# Regulator.net
KiCad netlist of a schematic drawn in Altium Designer
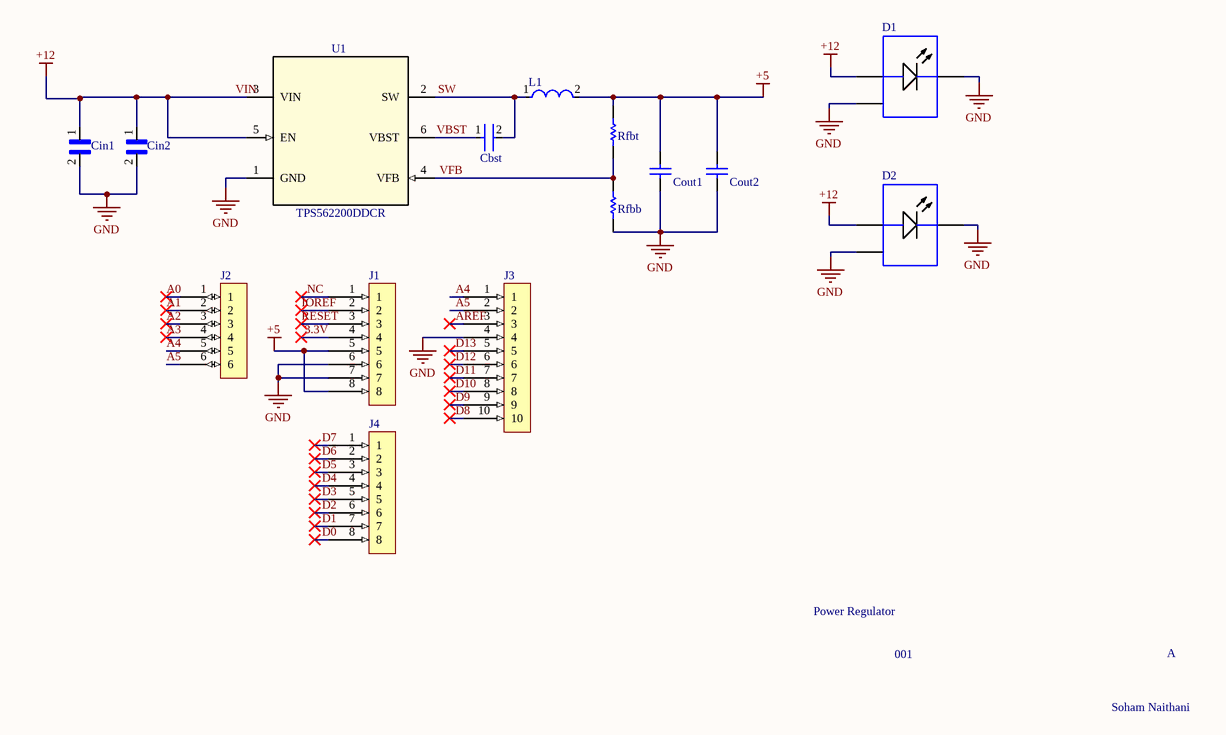
[diagram p0: Regulator.SchDoc]

(export (version "E")
  (design (tool "Eeschema 10.0.6"))
  (components
    (comp (ref "Cbst")
      (value "CC0805KRX7R8BB104")
      (footprint "FP-CC0805-0_85-MFG")
      (description "CAP CER 0.1UF 25V X7R 0805")
      (fields (field (name "TOLERANCE") "0.1") (field (name "MANUFACTURER") "Yageo"))
      (libsource (lib "Altium Content Vault") (part "11868f565c42a9108669ba33697ecf6"))
    )
    (comp (ref "Cin1")
      (value "C2012X5R1V106K085AC")
      (footprint "CAPC2012X100N")
      (description "10ÂµF Â±10% 35V Ceramic Capacitor X5R 0805 (2012 Metric)")
      (fields (field (name "MF") "TDK"))
      (libsource (lib "C2012X5R1V106K085AC") (part "C2012X5R1V106K085AC"))
    )
    (comp (ref "Cin2")
      (value "C2012X5R1V106K085AC")
      (footprint "CAPC2012X100N")
      (description "10ÂµF Â±10% 35V Ceramic Capacitor X5R 0805 (2012 Metric)")
      (fields (field (name "MF") "TDK"))
      (libsource (lib "C2012X5R1V106K085AC") (part "C2012X5R1V106K085AC"))
    )
    (comp (ref "Cout1")
      (value "C1608X5R1A226M080AC")
      (footprint "CAPC1608X100X20ML10")
      (description "Chip Capacitor, 22 uF, +/- 20%, 10 V, -55 to 85 degC, 0603 (1608 Metric), RoHS, Tape and Reel")
      (fields (field (name "MANUFACTURER") "TDK") (field (name "TOLERANCE") "±20%"))
      (libsource (lib "Altium Content Vault") (part "CAP-NP-2"))
    )
    (comp (ref "Cout2")
      (value "C1608X5R1A226M080AC")
      (footprint "CAPC1608X100X20ML10")
      (description "Chip Capacitor, 22 uF, +/- 20%, 10 V, -55 to 85 degC, 0603 (1608 Metric), RoHS, Tape and Reel")
      (fields (field (name "MANUFACTURER") "TDK") (field (name "TOLERANCE") "±20%"))
      (libsource (lib "Altium Content Vault") (part "CAP-NP-2"))
    )
    (comp (ref "D1")
      (value "MKRAWT-00-0000-0D0HG235H")
      (footprint "CREE-MK-R-2_V")
      (description "LED, White, 12 V, 2-Pin SMD, RoHS, Tape and Reel")
      (libsource (lib "Altium Content Vault") (part "LED_WHITE-3"))
    )
    (comp (ref "D2")
      (value "MKRAWT-00-0000-0D0HG235H")
      (footprint "CREE-MK-R-2_V")
      (description "LED, White, 12 V, 2-Pin SMD, RoHS, Tape and Reel")
      (libsource (lib "Altium Content Vault") (part "LED_WHITE-3"))
    )
    (comp (ref "J1")
      (value "8-Pin-Header")
      (footprint "8-Pin-Header-Footprint-1")
      (description "simple 8 pin header")
      (libsource (lib "Soham Naithani") (part "8-Pin-Header-Symbol-1"))
    )
    (comp (ref "J2")
      (value "6-Pin-Header")
      (footprint "6-PINHEADER-Footprint-1")
      (description "Simple 6 pin header")
      (libsource (lib "Soham Naithani") (part "6-PINHEADER-Symbol-1"))
    )
    (comp (ref "J3")
      (value "10-Pin-Header")
      (footprint "10-Pin-Header-Footprint-1")
      (description "Simple 10 pin header")
      (libsource (lib "Soham Naithani") (part "10-Pin-Header-Symbol-1"))
    )
    (comp (ref "J4")
      (value "8-Pin-Header")
      (footprint "8-Pin-Header-Footprint-1")
      (description "simple 8 pin header")
      (libsource (lib "Soham Naithani") (part "8-Pin-Header-Symbol-1"))
    )
    (comp (ref "L1")
      (value "NRS8030T3R3MJGJ")
      (footprint "FP-NRS8030-MFG")
      (description "Inductor Power Shielded Wirewound 3.3uH 20% 100KHz Ferrite 4.2A 24.7mΩ DCR T/R")
      (fields (field (name "TOLERANCE") "20%"))
      (libsource (lib "Altium Content Vault") (part "725321dda6339637d4d059423bc1c3c"))
    )
    (comp (ref "Rfbb")
      (value "ERJ2RKF1002X")
      (footprint "RESC1005X40X25LL05T05")
      (description "Chip Resistor, 10 KOhm, +/- 1%, 0.1 W, -55 to 155 degC, 0402 (1005 Metric), RoHS, Tape and Reel")
      (fields (field (name "TOLERANCE") "1%") (field (name "MANUFACTURER") "Panasonic"))
      (libsource (lib "Altium Content Vault") (part "RES-2"))
    )
    (comp (ref "Rfbt")
      (value "CRCW020156K2FNED")
      (footprint "RESC0603X28X15NL05T05")
      (fields (field (name "MANUFACTURER") "Vishay Dale"))
      (libsource (lib "Altium Content Vault") (part "RES"))
    )
    (comp (ref "U1")
      (value "TPS562200DDCR")
      (footprint "DDC0006A")
      (description "No Description Available")
      (fields
        (field (name "PARTNUMBER") "TPS562200DDC")
        (field (name "MANUFACTURER") "Texas Instruments")
        (field (name "COPYRIGHT") "Copyright (C) 2023 Ultra Librarian. All rights reserved.")
        (field (name "MODIFIEDDATE") "Not shown in title block")
        (field (name "APPROVEDBY") "Not shown in title block")
        (field (name "CHECKEDBY") "Not shown in title block")
        (field (name "AUTHOR") "Not shown in title block")
        (field (name "ENGINEER") "Not shown in title block")
        (field (name "SYMBOLCREATOR") "a0411947")
        (field (name "PUBLISHER") "Texas Instruments")
      )
      (libsource (lib "TPS562200DDCR") (part "TPS562200DDCR"))
    )
  )
  (nets
    (net (code "1") (name "+5") (class "Default")
      (node (ref "Cout1") (pin "2") (pinfunction "2_2") (pintype "passive"))
      (node (ref "Cout2") (pin "2") (pinfunction "2_2") (pintype "passive"))
      (node (ref "J1") (pin "5") (pinfunction "5_5") (pintype "input"))
      (node (ref "J1") (pin "8") (pinfunction "8_8") (pintype "input"))
      (node (ref "L1") (pin "2") (pinfunction "2_2") (pintype "passive"))
      (node (ref "Rfbt") (pin "2") (pinfunction "2_2") (pintype "passive"))
    )
    (net (code "2") (name "+12") (class "Default")
      (node (ref "Cin1") (pin "1") (pinfunction "1_1") (pintype "passive"))
      (node (ref "Cin2") (pin "1") (pinfunction "1_1") (pintype "passive"))
      (node (ref "D1") (pin "1") (pinfunction "A_1") (pintype "passive"))
      (node (ref "D2") (pin "1") (pinfunction "A_1") (pintype "passive"))
      (node (ref "U1") (pin "3") (pinfunction "VIN_3") (pintype "power_in"))
      (node (ref "U1") (pin "5") (pinfunction "EN_5") (pintype "input"))
    )
    (net (code "3") (name "/3.3V") (class "Default")
      (node (ref "J1") (pin "4") (pinfunction "4_4") (pintype "input+no_connect"))
    )
    (net (code "4") (name "/A0") (class "Default")
      (node (ref "J2") (pin "1") (pinfunction "1_1") (pintype "bidirectional+no_connect"))
    )
    (net (code "5") (name "/A1") (class "Default")
      (node (ref "J2") (pin "2") (pinfunction "2_2") (pintype "bidirectional+no_connect"))
    )
    (net (code "6") (name "/A2") (class "Default")
      (node (ref "J2") (pin "3") (pinfunction "3_3") (pintype "bidirectional+no_connect"))
    )
    (net (code "7") (name "/A3") (class "Default")
      (node (ref "J2") (pin "4") (pinfunction "4_4") (pintype "bidirectional+no_connect"))
    )
    (net (code "8") (name "/A4") (class "Default")
      (node (ref "J2") (pin "5") (pinfunction "5_5") (pintype "bidirectional"))
      (node (ref "J3") (pin "1") (pinfunction "1_1") (pintype "input"))
    )
    (net (code "9") (name "/A5") (class "Default")
      (node (ref "J2") (pin "6") (pinfunction "6_6") (pintype "bidirectional"))
      (node (ref "J3") (pin "2") (pinfunction "2_2") (pintype "input"))
    )
    (net (code "10") (name "/AREF") (class "Default")
      (node (ref "J3") (pin "3") (pinfunction "3_3") (pintype "input+no_connect"))
    )
    (net (code "11") (name "/D0") (class "Default")
      (node (ref "J4") (pin "8") (pinfunction "8_8") (pintype "input+no_connect"))
    )
    (net (code "12") (name "/D1") (class "Default")
      (node (ref "J4") (pin "7") (pinfunction "7_7") (pintype "input+no_connect"))
    )
    (net (code "13") (name "/D2") (class "Default")
      (node (ref "J4") (pin "6") (pinfunction "6_6") (pintype "input+no_connect"))
    )
    (net (code "14") (name "/D3") (class "Default")
      (node (ref "J4") (pin "5") (pinfunction "5_5") (pintype "input+no_connect"))
    )
    (net (code "15") (name "/D4") (class "Default")
      (node (ref "J4") (pin "4") (pinfunction "4_4") (pintype "input+no_connect"))
    )
    (net (code "16") (name "/D5") (class "Default")
      (node (ref "J4") (pin "3") (pinfunction "3_3") (pintype "input+no_connect"))
    )
    (net (code "17") (name "/D6") (class "Default")
      (node (ref "J4") (pin "2") (pinfunction "2_2") (pintype "input+no_connect"))
    )
    (net (code "18") (name "/D7") (class "Default")
      (node (ref "J4") (pin "1") (pinfunction "1_1") (pintype "input+no_connect"))
    )
    (net (code "19") (name "/D8") (class "Default")
      (node (ref "J3") (pin "10") (pinfunction "10_10") (pintype "input+no_connect"))
    )
    (net (code "20") (name "/D9") (class "Default")
      (node (ref "J3") (pin "9") (pinfunction "9_9") (pintype "input+no_connect"))
    )
    (net (code "21") (name "/D10") (class "Default")
      (node (ref "J3") (pin "8") (pinfunction "8_8") (pintype "input+no_connect"))
    )
    (net (code "22") (name "/D11") (class "Default")
      (node (ref "J3") (pin "7") (pinfunction "7_7") (pintype "input+no_connect"))
    )
    (net (code "23") (name "/D12") (class "Default")
      (node (ref "J3") (pin "6") (pinfunction "6_6") (pintype "input+no_connect"))
    )
    (net (code "24") (name "/D13") (class "Default")
      (node (ref "J3") (pin "5") (pinfunction "5_5") (pintype "input+no_connect"))
    )
    (net (code "25") (name "/IOREF") (class "Default")
      (node (ref "J1") (pin "2") (pinfunction "2_2") (pintype "input+no_connect"))
    )
    (net (code "26") (name "/NC") (class "Default")
      (node (ref "J1") (pin "1") (pinfunction "1_1") (pintype "input+no_connect"))
    )
    (net (code "27") (name "/RESET") (class "Default")
      (node (ref "J1") (pin "3") (pinfunction "3_3") (pintype "input+no_connect"))
    )
    (net (code "28") (name "/SW") (class "Default")
      (node (ref "Cbst") (pin "2") (pinfunction "2_2") (pintype "passive"))
      (node (ref "L1") (pin "1") (pinfunction "1_1") (pintype "passive"))
      (node (ref "U1") (pin "2") (pinfunction "SW_2") (pintype "power_in"))
    )
    (net (code "29") (name "/VBST") (class "Default")
      (node (ref "Cbst") (pin "1") (pinfunction "1_1") (pintype "passive"))
      (node (ref "U1") (pin "6") (pinfunction "VBST_6") (pintype "power_in"))
    )
    (net (code "30") (name "/VFB") (class "Default")
      (node (ref "Rfbb") (pin "2") (pinfunction "2_2") (pintype "passive"))
      (node (ref "Rfbt") (pin "1") (pinfunction "1_1") (pintype "passive"))
      (node (ref "U1") (pin "4") (pinfunction "VFB_4") (pintype "input"))
    )
    (net (code "31") (name "GND") (class "Default")
      (node (ref "Cin1") (pin "2") (pinfunction "2_2") (pintype "passive"))
      (node (ref "Cin2") (pin "2") (pinfunction "2_2") (pintype "passive"))
      (node (ref "Cout1") (pin "1") (pinfunction "1_1") (pintype "passive"))
      (node (ref "Cout2") (pin "1") (pinfunction "1_1") (pintype "passive"))
      (node (ref "D1") (pin "2") (pinfunction "K_2") (pintype "passive"))
      (node (ref "D1") (pin "3") (pinfunction "EP_3") (pintype "passive"))
      (node (ref "D2") (pin "2") (pinfunction "K_2") (pintype "passive"))
      (node (ref "D2") (pin "3") (pinfunction "EP_3") (pintype "passive"))
      (node (ref "J1") (pin "6") (pinfunction "6_6") (pintype "input"))
      (node (ref "J1") (pin "7") (pinfunction "7_7") (pintype "input"))
      (node (ref "J3") (pin "4") (pinfunction "4_4") (pintype "input"))
      (node (ref "Rfbb") (pin "1") (pinfunction "1_1") (pintype "passive"))
      (node (ref "U1") (pin "1") (pinfunction "GND_1") (pintype "power_in"))
    )
  )
)
